# power.net
KiCad netlist of a schematic drawn in Altium Designer
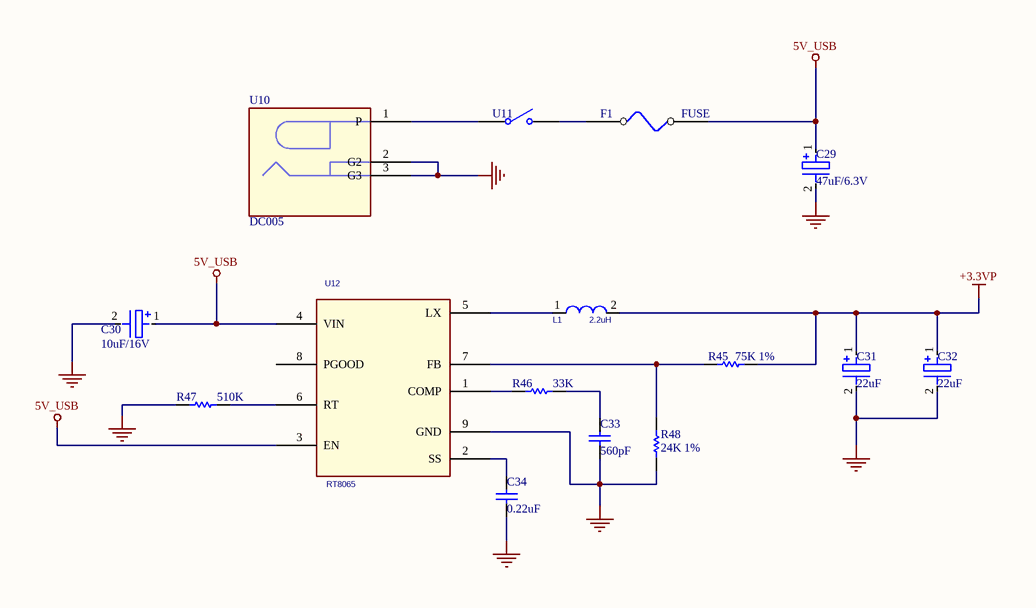
[diagram p0: power.SchDoc]

(export (version "E")
  (design (tool "Eeschema 10.0.6"))
  (components
    (comp (ref "C29")
      (value "47uF/6.3V")
      (footprint "C0805L")
      (fields (field (name "Comment") "Cap"))
      (libsource (lib "wooya_lib_footprint") (part "CAP3"))
    )
    (comp (ref "C30")
      (value "10uF/16V")
      (footprint "C0603L")
      (fields (field (name "Comment") "Cap"))
      (libsource (lib "wooya_lib_footprint") (part "CAP3"))
    )
    (comp (ref "C31")
      (value "22uF")
      (footprint "C0805L")
      (fields (field (name "Comment") "Cap"))
      (libsource (lib "wooya_lib_footprint") (part "CAP3"))
    )
    (comp (ref "C32")
      (value "22uF")
      (footprint "C0805L")
      (fields (field (name "Comment") "Cap"))
      (libsource (lib "wooya_lib_footprint") (part "CAP3"))
    )
    (comp (ref "C33")
      (value "560pF")
      (footprint "C0603L")
      (description "Capacitor (Semiconductor SIM Model)")
      (fields (field (name "Comment") "Cap Semi") (field (name "PUBLISHER") "Altium Limited"))
      (libsource (lib "Miscellaneous Devices") (part "Cap Semi"))
    )
    (comp (ref "C34")
      (value "0.22uF")
      (footprint "C0603L")
      (description "Capacitor (Semiconductor SIM Model)")
      (fields (field (name "Comment") "Cap Semi") (field (name "PUBLISHER") "Altium Limited"))
      (libsource (lib "Miscellaneous Devices") (part "Cap Semi"))
    )
    (comp (ref "F1")
      (value "FUSE")
      (footprint "FS_1206")
      (libsource (lib "wooya_lib_footprint") (part "FUSE"))
    )
    (comp (ref "L1") (value "2.2uH") (footprint "L3X3MM") (libsource (lib "*") (part "LQH32C_0_Dup1")))
    (comp (ref "R45")
      (value "75K 1%")
      (footprint "R0603L")
      (description "Semiconductor Resistor")
      (fields (field (name "Comment") "Res Semi") (field (name "PUBLISHER") "Altium Limited"))
      (libsource (lib "Miscellaneous Devices") (part "Res Semi"))
    )
    (comp (ref "R46")
      (value "33K")
      (footprint "R0603L")
      (description "Semiconductor Resistor")
      (fields (field (name "Comment") "Res Semi") (field (name "PUBLISHER") "Altium Limited"))
      (libsource (lib "Miscellaneous Devices") (part "Res Semi"))
    )
    (comp (ref "R47")
      (value "510K")
      (footprint "R0603L")
      (description "Semiconductor Resistor")
      (fields (field (name "Comment") "Res Semi") (field (name "PUBLISHER") "Altium Limited"))
      (libsource (lib "Miscellaneous Devices") (part "Res Semi"))
    )
    (comp (ref "R48")
      (value "24K 1%")
      (footprint "R0603L")
      (description "Semiconductor Resistor")
      (fields (field (name "Comment") "Res Semi") (field (name "PUBLISHER") "Altium Limited"))
      (libsource (lib "Miscellaneous Devices") (part "Res Semi"))
    )
    (comp (ref "U10")
      (value "DC005")
      (footprint "DC005")
      (libsource (lib "wooya_lib_footprint") (part "DC005"))
    )
    (comp (ref "U11")
      (value "switch_on_off")
      (footprint "switch_bodong")
      (libsource (lib "USB_SOUND") (part "switch_on_off"))
    )
    (comp (ref "U12") (value "RT8065") (libsource (lib "*") (part "RT8065")))
  )
  (nets
    (net (code "1") (name "+3.3VP") (class "Default")
      (node (ref "C31") (pin "1") (pinfunction "1_1") (pintype "passive"))
      (node (ref "C32") (pin "1") (pinfunction "1_1") (pintype "passive"))
      (node (ref "L1") (pin "2") (pinfunction "2_2") (pintype "passive"))
      (node (ref "R45") (pin "2") (pinfunction "2_2") (pintype "passive"))
    )
    (net (code "2") (name "5V_USB") (class "Default")
      (node (ref "C29") (pin "1") (pinfunction "1_1") (pintype "passive"))
      (node (ref "C30") (pin "1") (pinfunction "1_1") (pintype "passive"))
      (node (ref "F1") (pin "2") (pinfunction "2_2") (pintype "passive"))
      (node (ref "U12") (pin "3") (pinfunction "EN_3") (pintype "passive"))
      (node (ref "U12") (pin "4") (pinfunction "VIN_4") (pintype "passive"))
    )
    (net (code "3") (name "GND") (class "Default")
      (node (ref "C29") (pin "2") (pinfunction "2_2") (pintype "passive"))
      (node (ref "C30") (pin "2") (pinfunction "2_2") (pintype "passive"))
      (node (ref "C31") (pin "2") (pinfunction "2_2") (pintype "passive"))
      (node (ref "C32") (pin "2") (pinfunction "2_2") (pintype "passive"))
      (node (ref "C33") (pin "2") (pinfunction "2_2") (pintype "passive"))
      (node (ref "C34") (pin "2") (pinfunction "2_2") (pintype "passive"))
      (node (ref "R47") (pin "2") (pinfunction "2_2") (pintype "passive"))
      (node (ref "R48") (pin "2") (pinfunction "2_2") (pintype "passive"))
      (node (ref "U10") (pin "2") (pinfunction "G2_2") (pintype "passive"))
      (node (ref "U10") (pin "3") (pinfunction "G3_3") (pintype "passive"))
      (node (ref "U12") (pin "9") (pinfunction "GND_9") (pintype "passive"))
    )
    (net (code "4") (name "Net-(C33-Pad1)") (class "Default")
      (node (ref "C33") (pin "1") (pinfunction "1_1") (pintype "passive"))
      (node (ref "R46") (pin "1") (pinfunction "1_1") (pintype "passive"))
    )
    (net (code "5") (name "Net-(U10-P)") (class "Default")
      (node (ref "U10") (pin "1") (pinfunction "P_1") (pintype "passive"))
      (node (ref "U11") (pin "1") (pinfunction "COMMON_1") (pintype "passive"))
    )
    (net (code "6") (name "Net-(U11-NO)") (class "Default")
      (node (ref "F1") (pin "1") (pinfunction "1_1") (pintype "passive"))
      (node (ref "U11") (pin "2") (pinfunction "NO_2") (pintype "passive"))
    )
    (net (code "7") (name "Net-(U12-COMP)") (class "Default")
      (node (ref "R46") (pin "2") (pinfunction "2_2") (pintype "passive"))
      (node (ref "U12") (pin "1") (pinfunction "COMP_1") (pintype "passive"))
    )
    (net (code "8") (name "Net-(U12-FB)") (class "Default")
      (node (ref "R45") (pin "1") (pinfunction "1_1") (pintype "passive"))
      (node (ref "R48") (pin "1") (pinfunction "1_1") (pintype "passive"))
      (node (ref "U12") (pin "7") (pinfunction "FB_7") (pintype "passive"))
    )
    (net (code "9") (name "Net-(U12-LX)") (class "Default")
      (node (ref "L1") (pin "1") (pinfunction "1_1") (pintype "passive"))
      (node (ref "U12") (pin "5") (pinfunction "LX_5") (pintype "passive"))
    )
    (net (code "10") (name "Net-(U12-RT)") (class "Default")
      (node (ref "R47") (pin "1") (pinfunction "1_1") (pintype "passive"))
      (node (ref "U12") (pin "6") (pinfunction "RT_6") (pintype "passive"))
    )
    (net (code "11") (name "Net-(U12-SS)") (class "Default")
      (node (ref "C34") (pin "1") (pinfunction "1_1") (pintype "passive"))
      (node (ref "U12") (pin "2") (pinfunction "SS_2") (pintype "passive"))
    )
    (net (code "12") (name "unconnected-(U12-PGOOD-Pad8)") (class "Default")
      (node (ref "U12") (pin "8") (pinfunction "PGOOD_8") (pintype "passive"))
    )
  )
)
